# PGTN023_mix8.net
KiCad netlist of a schematic drawn in EAGLE
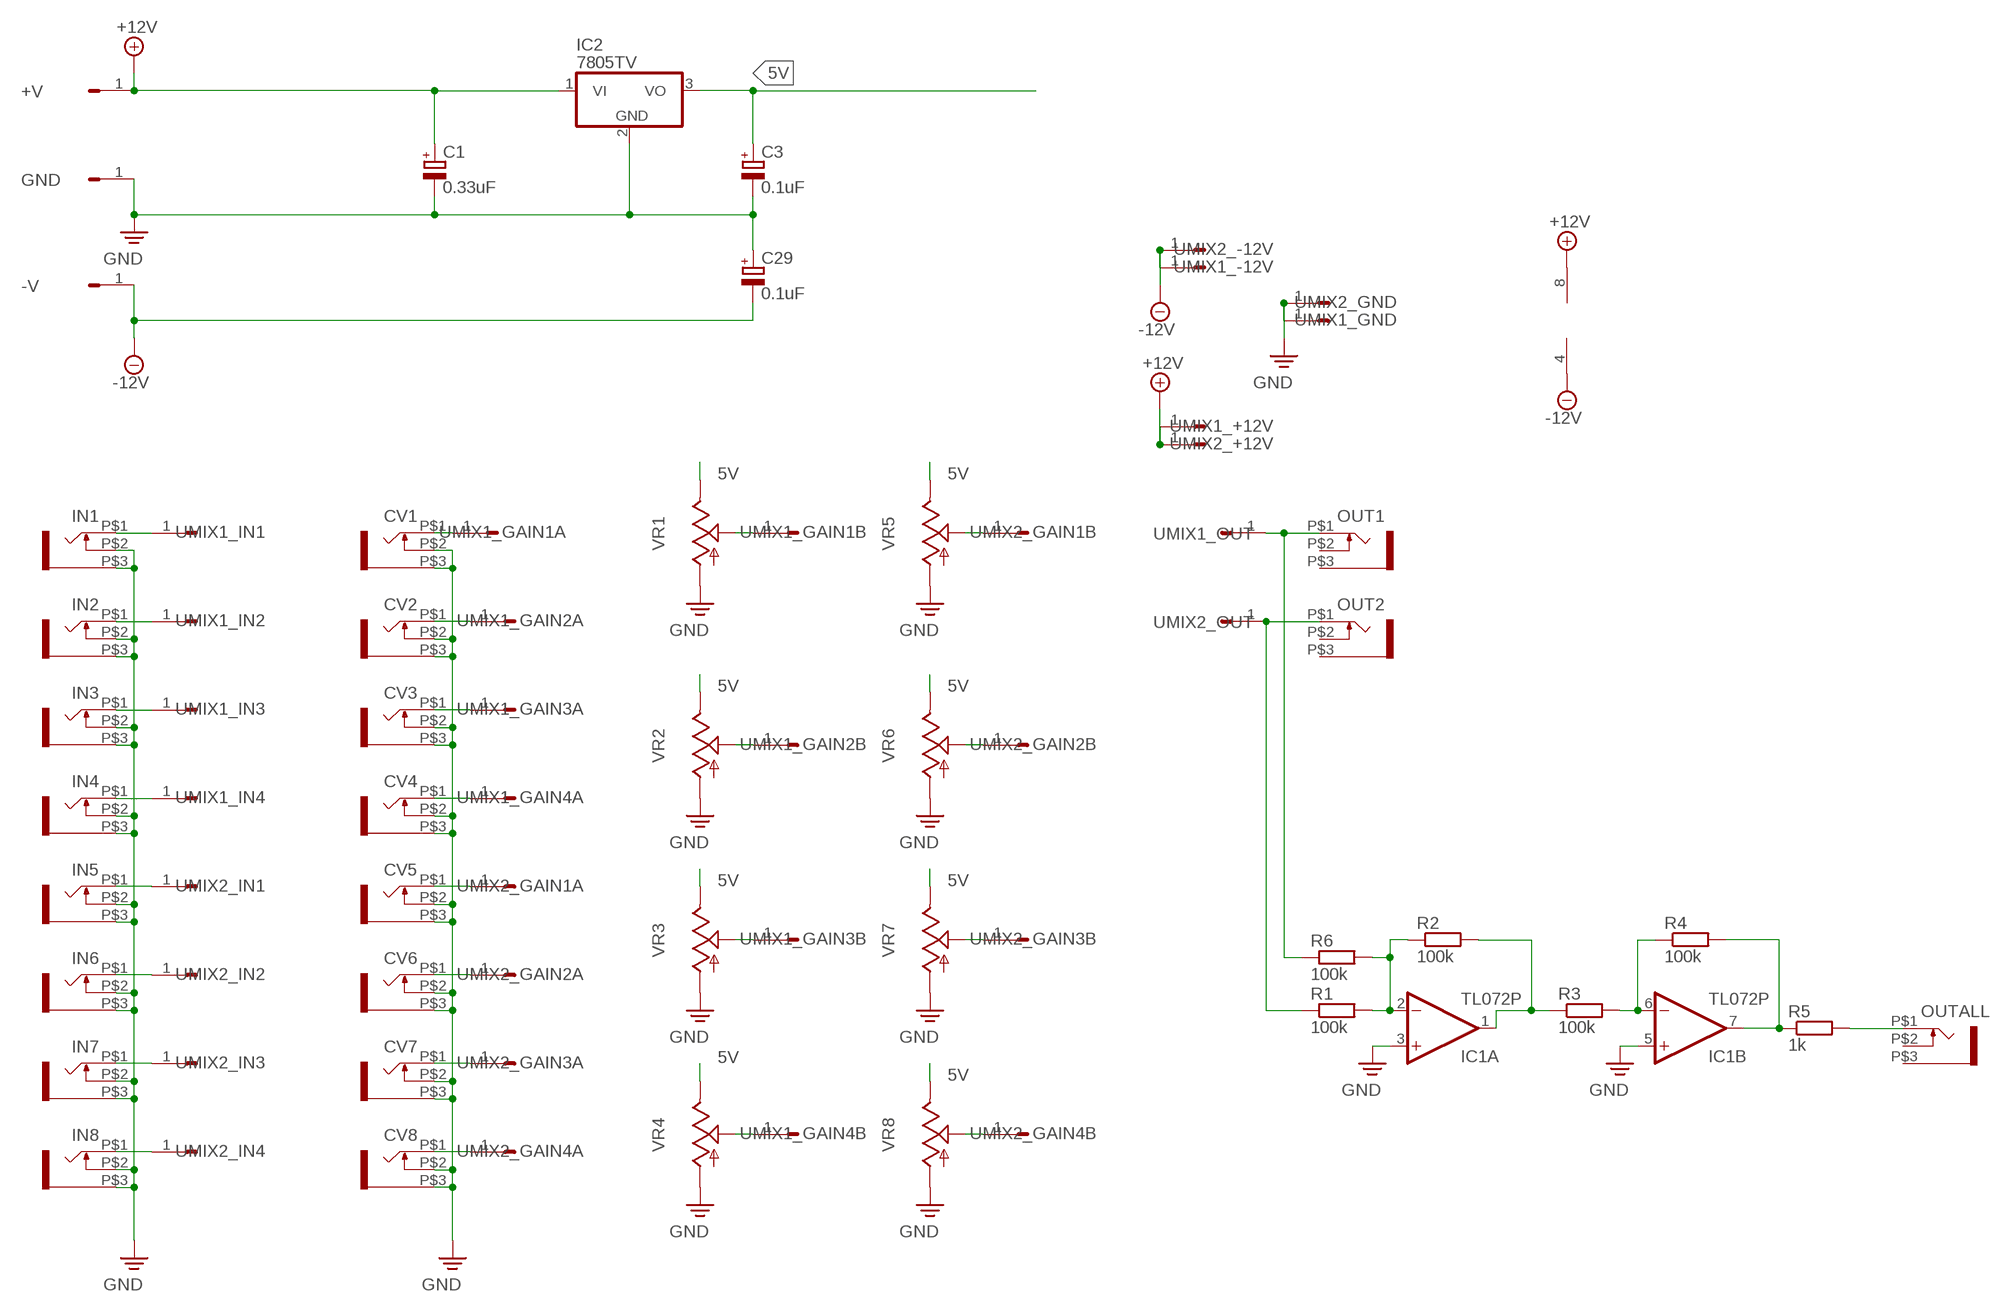
[diagram p0: schematic, sheet 1]

(export (version "E")
  (design (tool "Eeschema 10.0.6"))
  (components
    (comp (ref "+V")
      (value "HEADER/MALE/01")
      (footprint "eagle-import:HEADER_MALE_01")
      (fields (field (name "SPICEPREFIX") "X"))
      (libsource (lib "eagle-import") (part "HEADER/MALE/01"))
    )
    (comp (ref "-V")
      (value "HEADER/MALE/01")
      (footprint "eagle-import:HEADER_MALE_01")
      (fields (field (name "SPICEPREFIX") "X"))
      (libsource (lib "eagle-import") (part "HEADER/MALE/01"))
    )
    (comp (ref "C1")
      (value "0.33uF")
      (footprint "eagle-import:E2,5-6")
      (fields (field (name "SPICEPREFIX") "C"))
      (libsource (lib "eagle-import") (part "CAPACITOR/POLARIZEDE2.5-6"))
    )
    (comp (ref "C3")
      (value "0.1uF")
      (footprint "eagle-import:E2,5-6")
      (fields (field (name "SPICEPREFIX") "C"))
      (libsource (lib "eagle-import") (part "CAPACITOR/POLARIZEDE2.5-6"))
    )
    (comp (ref "C29")
      (value "0.1uF")
      (footprint "eagle-import:E2,5-6")
      (fields (field (name "SPICEPREFIX") "C"))
      (libsource (lib "eagle-import") (part "CAPACITOR/POLARIZEDE2.5-6"))
    )
    (comp (ref "CV1")
      (value "WQP-PJ301M-12_JACK")
      (footprint "eagle-import:WQP-PJ301M-12_JACK")
      (libsource (lib "eagle-import") (part "WQP-PJ301M-12_JACK"))
    )
    (comp (ref "CV2")
      (value "WQP-PJ301M-12_JACK")
      (footprint "eagle-import:WQP-PJ301M-12_JACK")
      (libsource (lib "eagle-import") (part "WQP-PJ301M-12_JACK"))
    )
    (comp (ref "CV3")
      (value "WQP-PJ301M-12_JACK")
      (footprint "eagle-import:WQP-PJ301M-12_JACK")
      (libsource (lib "eagle-import") (part "WQP-PJ301M-12_JACK"))
    )
    (comp (ref "CV4")
      (value "WQP-PJ301M-12_JACK")
      (footprint "eagle-import:WQP-PJ301M-12_JACK")
      (libsource (lib "eagle-import") (part "WQP-PJ301M-12_JACK"))
    )
    (comp (ref "CV5")
      (value "WQP-PJ301M-12_JACK")
      (footprint "eagle-import:WQP-PJ301M-12_JACK")
      (libsource (lib "eagle-import") (part "WQP-PJ301M-12_JACK"))
    )
    (comp (ref "CV6")
      (value "WQP-PJ301M-12_JACK")
      (footprint "eagle-import:WQP-PJ301M-12_JACK")
      (libsource (lib "eagle-import") (part "WQP-PJ301M-12_JACK"))
    )
    (comp (ref "CV7")
      (value "WQP-PJ301M-12_JACK")
      (footprint "eagle-import:WQP-PJ301M-12_JACK")
      (libsource (lib "eagle-import") (part "WQP-PJ301M-12_JACK"))
    )
    (comp (ref "CV8")
      (value "WQP-PJ301M-12_JACK")
      (footprint "eagle-import:WQP-PJ301M-12_JACK")
      (libsource (lib "eagle-import") (part "WQP-PJ301M-12_JACK"))
    )
    (comp (ref "GND")
      (value "HEADER/MALE/01")
      (footprint "eagle-import:HEADER_MALE_01")
      (fields (field (name "SPICEPREFIX") "X"))
      (libsource (lib "eagle-import") (part "HEADER/MALE/01"))
    )
    (comp (ref "IC1")
      (value "TL072P")
      (footprint "eagle-import:DIL08")
      (libsource (lib "eagle-import") (part "TL072P"))
    )
    (comp (ref "IC2")
      (value "7805TV")
      (footprint "eagle-import:TO220V")
      (libsource (lib "eagle-import") (part "78TV05"))
    )
    (comp (ref "IN1")
      (value "WQP-PJ301M-12_JACK")
      (footprint "eagle-import:WQP-PJ301M-12_JACK")
      (libsource (lib "eagle-import") (part "WQP-PJ301M-12_JACK"))
    )
    (comp (ref "IN2")
      (value "WQP-PJ301M-12_JACK")
      (footprint "eagle-import:WQP-PJ301M-12_JACK")
      (libsource (lib "eagle-import") (part "WQP-PJ301M-12_JACK"))
    )
    (comp (ref "IN3")
      (value "WQP-PJ301M-12_JACK")
      (footprint "eagle-import:WQP-PJ301M-12_JACK")
      (libsource (lib "eagle-import") (part "WQP-PJ301M-12_JACK"))
    )
    (comp (ref "IN4")
      (value "WQP-PJ301M-12_JACK")
      (footprint "eagle-import:WQP-PJ301M-12_JACK")
      (libsource (lib "eagle-import") (part "WQP-PJ301M-12_JACK"))
    )
    (comp (ref "IN5")
      (value "WQP-PJ301M-12_JACK")
      (footprint "eagle-import:WQP-PJ301M-12_JACK")
      (libsource (lib "eagle-import") (part "WQP-PJ301M-12_JACK"))
    )
    (comp (ref "IN6")
      (value "WQP-PJ301M-12_JACK")
      (footprint "eagle-import:WQP-PJ301M-12_JACK")
      (libsource (lib "eagle-import") (part "WQP-PJ301M-12_JACK"))
    )
    (comp (ref "IN7")
      (value "WQP-PJ301M-12_JACK")
      (footprint "eagle-import:WQP-PJ301M-12_JACK")
      (libsource (lib "eagle-import") (part "WQP-PJ301M-12_JACK"))
    )
    (comp (ref "IN8")
      (value "WQP-PJ301M-12_JACK")
      (footprint "eagle-import:WQP-PJ301M-12_JACK")
      (libsource (lib "eagle-import") (part "WQP-PJ301M-12_JACK"))
    )
    (comp (ref "OUT1")
      (value "WQP-PJ301M-12_JACK")
      (footprint "eagle-import:WQP-PJ301M-12_JACK")
      (libsource (lib "eagle-import") (part "WQP-PJ301M-12_JACK"))
    )
    (comp (ref "OUT2")
      (value "WQP-PJ301M-12_JACK")
      (footprint "eagle-import:WQP-PJ301M-12_JACK")
      (libsource (lib "eagle-import") (part "WQP-PJ301M-12_JACK"))
    )
    (comp (ref "OUTALL")
      (value "WQP-PJ301M-12_JACK")
      (footprint "eagle-import:WQP-PJ301M-12_JACK")
      (libsource (lib "eagle-import") (part "WQP-PJ301M-12_JACK"))
    )
    (comp (ref "R1")
      (value "100k")
      (footprint "eagle-import:RESISTOR_7.5")
      (libsource (lib "eagle-import") (part "RESISTORRESISTOR/UPRIGHT/7.5"))
    )
    (comp (ref "R2")
      (value "100k")
      (footprint "eagle-import:RESISTOR_7.5")
      (libsource (lib "eagle-import") (part "RESISTORRESISTOR/UPRIGHT/7.5"))
    )
    (comp (ref "R3")
      (value "100k")
      (footprint "eagle-import:RESISTOR_7.5")
      (libsource (lib "eagle-import") (part "RESISTORRESISTOR/UPRIGHT/7.5"))
    )
    (comp (ref "R4")
      (value "100k")
      (footprint "eagle-import:RESISTOR_7.5")
      (libsource (lib "eagle-import") (part "RESISTORRESISTOR/UPRIGHT/7.5"))
    )
    (comp (ref "R5")
      (value "1k")
      (footprint "eagle-import:RESISTOR_7.5")
      (libsource (lib "eagle-import") (part "RESISTORRESISTOR/UPRIGHT/7.5"))
    )
    (comp (ref "R6")
      (value "100k")
      (footprint "eagle-import:RESISTOR_7.5")
      (libsource (lib "eagle-import") (part "RESISTORRESISTOR/UPRIGHT/7.5"))
    )
    (comp (ref "UMIX1_+12V")
      (value "HEADER/MALE/01")
      (footprint "eagle-import:HEADER_MALE_01")
      (fields (field (name "SPICEPREFIX") "X"))
      (libsource (lib "eagle-import") (part "HEADER/MALE/01"))
    )
    (comp (ref "UMIX1_-12V")
      (value "HEADER/MALE/01")
      (footprint "eagle-import:HEADER_MALE_01")
      (fields (field (name "SPICEPREFIX") "X"))
      (libsource (lib "eagle-import") (part "HEADER/MALE/01"))
    )
    (comp (ref "UMIX1_GAIN1A")
      (value "HEADER/MALE/01")
      (footprint "eagle-import:HEADER_MALE_01")
      (fields (field (name "SPICEPREFIX") "X"))
      (libsource (lib "eagle-import") (part "HEADER/MALE/01"))
    )
    (comp (ref "UMIX1_GAIN1B")
      (value "HEADER/MALE/01")
      (footprint "eagle-import:HEADER_MALE_01")
      (fields (field (name "SPICEPREFIX") "X"))
      (libsource (lib "eagle-import") (part "HEADER/MALE/01"))
    )
    (comp (ref "UMIX1_GAIN2A")
      (value "HEADER/MALE/01")
      (footprint "eagle-import:HEADER_MALE_01")
      (fields (field (name "SPICEPREFIX") "X"))
      (libsource (lib "eagle-import") (part "HEADER/MALE/01"))
    )
    (comp (ref "UMIX1_GAIN2B")
      (value "HEADER/MALE/01")
      (footprint "eagle-import:HEADER_MALE_01")
      (fields (field (name "SPICEPREFIX") "X"))
      (libsource (lib "eagle-import") (part "HEADER/MALE/01"))
    )
    (comp (ref "UMIX1_GAIN3A")
      (value "HEADER/MALE/01")
      (footprint "eagle-import:HEADER_MALE_01")
      (fields (field (name "SPICEPREFIX") "X"))
      (libsource (lib "eagle-import") (part "HEADER/MALE/01"))
    )
    (comp (ref "UMIX1_GAIN3B")
      (value "HEADER/MALE/01")
      (footprint "eagle-import:HEADER_MALE_01")
      (fields (field (name "SPICEPREFIX") "X"))
      (libsource (lib "eagle-import") (part "HEADER/MALE/01"))
    )
    (comp (ref "UMIX1_GAIN4A")
      (value "HEADER/MALE/01")
      (footprint "eagle-import:HEADER_MALE_01")
      (fields (field (name "SPICEPREFIX") "X"))
      (libsource (lib "eagle-import") (part "HEADER/MALE/01"))
    )
    (comp (ref "UMIX1_GAIN4B")
      (value "HEADER/MALE/01")
      (footprint "eagle-import:HEADER_MALE_01")
      (fields (field (name "SPICEPREFIX") "X"))
      (libsource (lib "eagle-import") (part "HEADER/MALE/01"))
    )
    (comp (ref "UMIX1_GND")
      (value "HEADER/MALE/01")
      (footprint "eagle-import:HEADER_MALE_01")
      (fields (field (name "SPICEPREFIX") "X"))
      (libsource (lib "eagle-import") (part "HEADER/MALE/01"))
    )
    (comp (ref "UMIX1_IN1")
      (value "HEADER/MALE/01")
      (footprint "eagle-import:HEADER_MALE_01")
      (fields (field (name "SPICEPREFIX") "X"))
      (libsource (lib "eagle-import") (part "HEADER/MALE/01"))
    )
    (comp (ref "UMIX1_IN2")
      (value "HEADER/MALE/01")
      (footprint "eagle-import:HEADER_MALE_01")
      (fields (field (name "SPICEPREFIX") "X"))
      (libsource (lib "eagle-import") (part "HEADER/MALE/01"))
    )
    (comp (ref "UMIX1_IN3")
      (value "HEADER/MALE/01")
      (footprint "eagle-import:HEADER_MALE_01")
      (fields (field (name "SPICEPREFIX") "X"))
      (libsource (lib "eagle-import") (part "HEADER/MALE/01"))
    )
    (comp (ref "UMIX1_IN4")
      (value "HEADER/MALE/01")
      (footprint "eagle-import:HEADER_MALE_01")
      (fields (field (name "SPICEPREFIX") "X"))
      (libsource (lib "eagle-import") (part "HEADER/MALE/01"))
    )
    (comp (ref "UMIX1_OUT")
      (value "HEADER/MALE/01")
      (footprint "eagle-import:HEADER_MALE_01")
      (fields (field (name "SPICEPREFIX") "X"))
      (libsource (lib "eagle-import") (part "HEADER/MALE/01"))
    )
    (comp (ref "UMIX2_+12V")
      (value "HEADER/MALE/01")
      (footprint "eagle-import:HEADER_MALE_01")
      (fields (field (name "SPICEPREFIX") "X"))
      (libsource (lib "eagle-import") (part "HEADER/MALE/01"))
    )
    (comp (ref "UMIX2_-12V")
      (value "HEADER/MALE/01")
      (footprint "eagle-import:HEADER_MALE_01")
      (fields (field (name "SPICEPREFIX") "X"))
      (libsource (lib "eagle-import") (part "HEADER/MALE/01"))
    )
    (comp (ref "UMIX2_GAIN1A")
      (value "HEADER/MALE/01")
      (footprint "eagle-import:HEADER_MALE_01")
      (fields (field (name "SPICEPREFIX") "X"))
      (libsource (lib "eagle-import") (part "HEADER/MALE/01"))
    )
    (comp (ref "UMIX2_GAIN1B")
      (value "HEADER/MALE/01")
      (footprint "eagle-import:HEADER_MALE_01")
      (fields (field (name "SPICEPREFIX") "X"))
      (libsource (lib "eagle-import") (part "HEADER/MALE/01"))
    )
    (comp (ref "UMIX2_GAIN2A")
      (value "HEADER/MALE/01")
      (footprint "eagle-import:HEADER_MALE_01")
      (fields (field (name "SPICEPREFIX") "X"))
      (libsource (lib "eagle-import") (part "HEADER/MALE/01"))
    )
    (comp (ref "UMIX2_GAIN2B")
      (value "HEADER/MALE/01")
      (footprint "eagle-import:HEADER_MALE_01")
      (fields (field (name "SPICEPREFIX") "X"))
      (libsource (lib "eagle-import") (part "HEADER/MALE/01"))
    )
    (comp (ref "UMIX2_GAIN3A")
      (value "HEADER/MALE/01")
      (footprint "eagle-import:HEADER_MALE_01")
      (fields (field (name "SPICEPREFIX") "X"))
      (libsource (lib "eagle-import") (part "HEADER/MALE/01"))
    )
    (comp (ref "UMIX2_GAIN3B")
      (value "HEADER/MALE/01")
      (footprint "eagle-import:HEADER_MALE_01")
      (fields (field (name "SPICEPREFIX") "X"))
      (libsource (lib "eagle-import") (part "HEADER/MALE/01"))
    )
    (comp (ref "UMIX2_GAIN4A")
      (value "HEADER/MALE/01")
      (footprint "eagle-import:HEADER_MALE_01")
      (fields (field (name "SPICEPREFIX") "X"))
      (libsource (lib "eagle-import") (part "HEADER/MALE/01"))
    )
    (comp (ref "UMIX2_GAIN4B")
      (value "HEADER/MALE/01")
      (footprint "eagle-import:HEADER_MALE_01")
      (fields (field (name "SPICEPREFIX") "X"))
      (libsource (lib "eagle-import") (part "HEADER/MALE/01"))
    )
    (comp (ref "UMIX2_GND")
      (value "HEADER/MALE/01")
      (footprint "eagle-import:HEADER_MALE_01")
      (fields (field (name "SPICEPREFIX") "X"))
      (libsource (lib "eagle-import") (part "HEADER/MALE/01"))
    )
    (comp (ref "UMIX2_IN1")
      (value "HEADER/MALE/01")
      (footprint "eagle-import:HEADER_MALE_01")
      (fields (field (name "SPICEPREFIX") "X"))
      (libsource (lib "eagle-import") (part "HEADER/MALE/01"))
    )
    (comp (ref "UMIX2_IN2")
      (value "HEADER/MALE/01")
      (footprint "eagle-import:HEADER_MALE_01")
      (fields (field (name "SPICEPREFIX") "X"))
      (libsource (lib "eagle-import") (part "HEADER/MALE/01"))
    )
    (comp (ref "UMIX2_IN3")
      (value "HEADER/MALE/01")
      (footprint "eagle-import:HEADER_MALE_01")
      (fields (field (name "SPICEPREFIX") "X"))
      (libsource (lib "eagle-import") (part "HEADER/MALE/01"))
    )
    (comp (ref "UMIX2_IN4")
      (value "HEADER/MALE/01")
      (footprint "eagle-import:HEADER_MALE_01")
      (fields (field (name "SPICEPREFIX") "X"))
      (libsource (lib "eagle-import") (part "HEADER/MALE/01"))
    )
    (comp (ref "UMIX2_OUT")
      (value "HEADER/MALE/01")
      (footprint "eagle-import:HEADER_MALE_01")
      (fields (field (name "SPICEPREFIX") "X"))
      (libsource (lib "eagle-import") (part "HEADER/MALE/01"))
    )
    (comp (ref "VR1")
      (value "9MM_SNAP-IN_POT_")
      (footprint "eagle-import:9MM_SNAP-IN_POT")
      (libsource (lib "eagle-import") (part "9MM_SNAP-IN_POT_"))
    )
    (comp (ref "VR2")
      (value "9MM_SNAP-IN_POT_")
      (footprint "eagle-import:9MM_SNAP-IN_POT")
      (libsource (lib "eagle-import") (part "9MM_SNAP-IN_POT_"))
    )
    (comp (ref "VR3")
      (value "9MM_SNAP-IN_POT_")
      (footprint "eagle-import:9MM_SNAP-IN_POT")
      (libsource (lib "eagle-import") (part "9MM_SNAP-IN_POT_"))
    )
    (comp (ref "VR4")
      (value "9MM_SNAP-IN_POT_")
      (footprint "eagle-import:9MM_SNAP-IN_POT")
      (libsource (lib "eagle-import") (part "9MM_SNAP-IN_POT_"))
    )
    (comp (ref "VR5")
      (value "9MM_SNAP-IN_POT_")
      (footprint "eagle-import:9MM_SNAP-IN_POT")
      (libsource (lib "eagle-import") (part "9MM_SNAP-IN_POT_"))
    )
    (comp (ref "VR6")
      (value "9MM_SNAP-IN_POT_")
      (footprint "eagle-import:9MM_SNAP-IN_POT")
      (libsource (lib "eagle-import") (part "9MM_SNAP-IN_POT_"))
    )
    (comp (ref "VR7")
      (value "9MM_SNAP-IN_POT_")
      (footprint "eagle-import:9MM_SNAP-IN_POT")
      (libsource (lib "eagle-import") (part "9MM_SNAP-IN_POT_"))
    )
    (comp (ref "VR8")
      (value "9MM_SNAP-IN_POT_")
      (footprint "eagle-import:9MM_SNAP-IN_POT")
      (libsource (lib "eagle-import") (part "9MM_SNAP-IN_POT_"))
    )
  )
  (nets
    (net (code "1") (name "+12V") (class "Default")
      (node (ref "+V") (pin "1") (pinfunction "3_1") (pintype "passive"))
      (node (ref "C1") (pin "+") (pinfunction "+_+") (pintype "passive"))
      (node (ref "IC1") (pin "8") (pinfunction "V+_8") (pintype "power_in"))
      (node (ref "IC2") (pin "1") (pinfunction "VI_1") (pintype "input"))
      (node (ref "UMIX1_+12V") (pin "1") (pinfunction "3_1") (pintype "passive"))
      (node (ref "UMIX2_+12V") (pin "1") (pinfunction "3_1") (pintype "passive"))
    )
    (net (code "2") (name "-12V") (class "Default")
      (node (ref "-V") (pin "1") (pinfunction "3_1") (pintype "passive"))
      (node (ref "C29") (pin "-") (pinfunction "-_-") (pintype "passive"))
      (node (ref "IC1") (pin "4") (pinfunction "V-_4") (pintype "power_in"))
      (node (ref "UMIX1_-12V") (pin "1") (pinfunction "3_1") (pintype "passive"))
      (node (ref "UMIX2_-12V") (pin "1") (pinfunction "3_1") (pintype "passive"))
    )
    (net (code "3") (name "5V") (class "Default")
      (node (ref "C3") (pin "+") (pinfunction "+_+") (pintype "passive"))
      (node (ref "IC2") (pin "3") (pinfunction "VO_3") (pintype "passive"))
      (node (ref "VR1") (pin "3") (pinfunction "E_3") (pintype "passive"))
      (node (ref "VR2") (pin "3") (pinfunction "E_3") (pintype "passive"))
      (node (ref "VR3") (pin "3") (pinfunction "E_3") (pintype "passive"))
      (node (ref "VR4") (pin "3") (pinfunction "E_3") (pintype "passive"))
      (node (ref "VR5") (pin "3") (pinfunction "E_3") (pintype "passive"))
      (node (ref "VR6") (pin "3") (pinfunction "E_3") (pintype "passive"))
      (node (ref "VR7") (pin "3") (pinfunction "E_3") (pintype "passive"))
      (node (ref "VR8") (pin "3") (pinfunction "E_3") (pintype "passive"))
    )
    (net (code "4") (name "GND") (class "Default")
      (node (ref "C1") (pin "-") (pinfunction "-_-") (pintype "passive"))
      (node (ref "C29") (pin "+") (pinfunction "+_+") (pintype "passive"))
      (node (ref "C3") (pin "-") (pinfunction "-_-") (pintype "passive"))
      (node (ref "CV1") (pin "P$2") (pinfunction "3_P$2") (pintype "passive"))
      (node (ref "CV1") (pin "P$3") (pinfunction "1_P$3") (pintype "passive"))
      (node (ref "CV2") (pin "P$2") (pinfunction "3_P$2") (pintype "passive"))
      (node (ref "CV2") (pin "P$3") (pinfunction "1_P$3") (pintype "passive"))
      (node (ref "CV3") (pin "P$2") (pinfunction "3_P$2") (pintype "passive"))
      (node (ref "CV3") (pin "P$3") (pinfunction "1_P$3") (pintype "passive"))
      (node (ref "CV4") (pin "P$2") (pinfunction "3_P$2") (pintype "passive"))
      (node (ref "CV4") (pin "P$3") (pinfunction "1_P$3") (pintype "passive"))
      (node (ref "CV5") (pin "P$2") (pinfunction "3_P$2") (pintype "passive"))
      (node (ref "CV5") (pin "P$3") (pinfunction "1_P$3") (pintype "passive"))
      (node (ref "CV6") (pin "P$2") (pinfunction "3_P$2") (pintype "passive"))
      (node (ref "CV6") (pin "P$3") (pinfunction "1_P$3") (pintype "passive"))
      (node (ref "CV7") (pin "P$2") (pinfunction "3_P$2") (pintype "passive"))
      (node (ref "CV7") (pin "P$3") (pinfunction "1_P$3") (pintype "passive"))
      (node (ref "CV8") (pin "P$2") (pinfunction "3_P$2") (pintype "passive"))
      (node (ref "CV8") (pin "P$3") (pinfunction "1_P$3") (pintype "passive"))
      (node (ref "GND") (pin "1") (pinfunction "3_1") (pintype "passive"))
      (node (ref "IC1") (pin "3") (pinfunction "+IN_3") (pintype "input"))
      (node (ref "IC1") (pin "5") (pinfunction "+IN_5") (pintype "input"))
      (node (ref "IC2") (pin "2") (pinfunction "GND_2") (pintype "passive"))
      (node (ref "IN1") (pin "P$2") (pinfunction "3_P$2") (pintype "passive"))
      (node (ref "IN1") (pin "P$3") (pinfunction "1_P$3") (pintype "passive"))
      (node (ref "IN2") (pin "P$2") (pinfunction "3_P$2") (pintype "passive"))
      (node (ref "IN2") (pin "P$3") (pinfunction "1_P$3") (pintype "passive"))
      (node (ref "IN3") (pin "P$2") (pinfunction "3_P$2") (pintype "passive"))
      (node (ref "IN3") (pin "P$3") (pinfunction "1_P$3") (pintype "passive"))
      (node (ref "IN4") (pin "P$2") (pinfunction "3_P$2") (pintype "passive"))
      (node (ref "IN4") (pin "P$3") (pinfunction "1_P$3") (pintype "passive"))
      (node (ref "IN5") (pin "P$2") (pinfunction "3_P$2") (pintype "passive"))
      (node (ref "IN5") (pin "P$3") (pinfunction "1_P$3") (pintype "passive"))
      (node (ref "IN6") (pin "P$2") (pinfunction "3_P$2") (pintype "passive"))
      (node (ref "IN6") (pin "P$3") (pinfunction "1_P$3") (pintype "passive"))
      (node (ref "IN7") (pin "P$2") (pinfunction "3_P$2") (pintype "passive"))
      (node (ref "IN7") (pin "P$3") (pinfunction "1_P$3") (pintype "passive"))
      (node (ref "IN8") (pin "P$2") (pinfunction "3_P$2") (pintype "passive"))
      (node (ref "IN8") (pin "P$3") (pinfunction "1_P$3") (pintype "passive"))
      (node (ref "UMIX1_GND") (pin "1") (pinfunction "3_1") (pintype "passive"))
      (node (ref "UMIX2_GND") (pin "1") (pinfunction "3_1") (pintype "passive"))
      (node (ref "VR1") (pin "1") (pinfunction "A_1") (pintype "passive"))
      (node (ref "VR2") (pin "1") (pinfunction "A_1") (pintype "passive"))
      (node (ref "VR3") (pin "1") (pinfunction "A_1") (pintype "passive"))
      (node (ref "VR4") (pin "1") (pinfunction "A_1") (pintype "passive"))
      (node (ref "VR5") (pin "1") (pinfunction "A_1") (pintype "passive"))
      (node (ref "VR6") (pin "1") (pinfunction "A_1") (pintype "passive"))
      (node (ref "VR7") (pin "1") (pinfunction "A_1") (pintype "passive"))
      (node (ref "VR8") (pin "1") (pinfunction "A_1") (pintype "passive"))
    )
    (net (code "5") (name "Net-(CV1-2)") (class "Default")
      (node (ref "CV1") (pin "P$1") (pinfunction "2_P$1") (pintype "passive"))
      (node (ref "UMIX1_GAIN1A") (pin "1") (pinfunction "3_1") (pintype "passive"))
    )
    (net (code "6") (name "Net-(CV2-2)") (class "Default")
      (node (ref "CV2") (pin "P$1") (pinfunction "2_P$1") (pintype "passive"))
      (node (ref "UMIX1_GAIN2A") (pin "1") (pinfunction "3_1") (pintype "passive"))
    )
    (net (code "7") (name "Net-(CV3-2)") (class "Default")
      (node (ref "CV3") (pin "P$1") (pinfunction "2_P$1") (pintype "passive"))
      (node (ref "UMIX1_GAIN3A") (pin "1") (pinfunction "3_1") (pintype "passive"))
    )
    (net (code "8") (name "Net-(CV4-2)") (class "Default")
      (node (ref "CV4") (pin "P$1") (pinfunction "2_P$1") (pintype "passive"))
      (node (ref "UMIX1_GAIN4A") (pin "1") (pinfunction "3_1") (pintype "passive"))
    )
    (net (code "9") (name "Net-(CV5-2)") (class "Default")
      (node (ref "CV5") (pin "P$1") (pinfunction "2_P$1") (pintype "passive"))
      (node (ref "UMIX2_GAIN1A") (pin "1") (pinfunction "3_1") (pintype "passive"))
    )
    (net (code "10") (name "Net-(CV6-2)") (class "Default")
      (node (ref "CV6") (pin "P$1") (pinfunction "2_P$1") (pintype "passive"))
      (node (ref "UMIX2_GAIN2A") (pin "1") (pinfunction "3_1") (pintype "passive"))
    )
    (net (code "11") (name "Net-(CV7-2)") (class "Default")
      (node (ref "CV7") (pin "P$1") (pinfunction "2_P$1") (pintype "passive"))
      (node (ref "UMIX2_GAIN3A") (pin "1") (pinfunction "3_1") (pintype "passive"))
    )
    (net (code "12") (name "Net-(CV8-2)") (class "Default")
      (node (ref "CV8") (pin "P$1") (pinfunction "2_P$1") (pintype "passive"))
      (node (ref "UMIX2_GAIN4A") (pin "1") (pinfunction "3_1") (pintype "passive"))
    )
    (net (code "13") (name "Net-(IC1A--IN)") (class "Default")
      (node (ref "IC1") (pin "2") (pinfunction "-IN_2") (pintype "input"))
      (node (ref "R1") (pin "2") (pinfunction "2_2") (pintype "passive"))
      (node (ref "R2") (pin "1") (pinfunction "1_1") (pintype "passive"))
      (node (ref "R6") (pin "2") (pinfunction "2_2") (pintype "passive"))
    )
    (net (code "14") (name "Net-(IC1A-OUT)") (class "Default")
      (node (ref "IC1") (pin "1") (pinfunction "OUT_1") (pintype "output"))
      (node (ref "R2") (pin "2") (pinfunction "2_2") (pintype "passive"))
      (node (ref "R3") (pin "1") (pinfunction "1_1") (pintype "passive"))
    )
    (net (code "15") (name "Net-(IC1B--IN)") (class "Default")
      (node (ref "IC1") (pin "6") (pinfunction "-IN_6") (pintype "input"))
      (node (ref "R3") (pin "2") (pinfunction "2_2") (pintype "passive"))
      (node (ref "R4") (pin "1") (pinfunction "1_1") (pintype "passive"))
    )
    (net (code "16") (name "Net-(IC1B-OUT)") (class "Default")
      (node (ref "IC1") (pin "7") (pinfunction "OUT_7") (pintype "output"))
      (node (ref "R4") (pin "2") (pinfunction "2_2") (pintype "passive"))
      (node (ref "R5") (pin "1") (pinfunction "1_1") (pintype "passive"))
    )
    (net (code "17") (name "Net-(IN1-2)") (class "Default")
      (node (ref "IN1") (pin "P$1") (pinfunction "2_P$1") (pintype "passive"))
      (node (ref "UMIX1_IN1") (pin "1") (pinfunction "3_1") (pintype "passive"))
    )
    (net (code "18") (name "Net-(IN2-2)") (class "Default")
      (node (ref "IN2") (pin "P$1") (pinfunction "2_P$1") (pintype "passive"))
      (node (ref "UMIX1_IN2") (pin "1") (pinfunction "3_1") (pintype "passive"))
    )
    (net (code "19") (name "Net-(IN3-2)") (class "Default")
      (node (ref "IN3") (pin "P$1") (pinfunction "2_P$1") (pintype "passive"))
      (node (ref "UMIX1_IN3") (pin "1") (pinfunction "3_1") (pintype "passive"))
    )
    (net (code "20") (name "Net-(IN4-2)") (class "Default")
      (node (ref "IN4") (pin "P$1") (pinfunction "2_P$1") (pintype "passive"))
      (node (ref "UMIX1_IN4") (pin "1") (pinfunction "3_1") (pintype "passive"))
    )
    (net (code "21") (name "Net-(IN5-2)") (class "Default")
      (node (ref "IN5") (pin "P$1") (pinfunction "2_P$1") (pintype "passive"))
      (node (ref "UMIX2_IN1") (pin "1") (pinfunction "3_1") (pintype "passive"))
    )
    (net (code "22") (name "Net-(IN6-2)") (class "Default")
      (node (ref "IN6") (pin "P$1") (pinfunction "2_P$1") (pintype "passive"))
      (node (ref "UMIX2_IN2") (pin "1") (pinfunction "3_1") (pintype "passive"))
    )
    (net (code "23") (name "Net-(IN7-2)") (class "Default")
      (node (ref "IN7") (pin "P$1") (pinfunction "2_P$1") (pintype "passive"))
      (node (ref "UMIX2_IN3") (pin "1") (pinfunction "3_1") (pintype "passive"))
    )
    (net (code "24") (name "Net-(IN8-2)") (class "Default")
      (node (ref "IN8") (pin "P$1") (pinfunction "2_P$1") (pintype "passive"))
      (node (ref "UMIX2_IN4") (pin "1") (pinfunction "3_1") (pintype "passive"))
    )
    (net (code "25") (name "Net-(OUT1-2)") (class "Default")
      (node (ref "OUT1") (pin "P$1") (pinfunction "2_P$1") (pintype "passive"))
      (node (ref "R6") (pin "1") (pinfunction "1_1") (pintype "passive"))
      (node (ref "UMIX1_OUT") (pin "1") (pinfunction "3_1") (pintype "passive"))
    )
    (net (code "26") (name "Net-(OUT2-2)") (class "Default")
      (node (ref "OUT2") (pin "P$1") (pinfunction "2_P$1") (pintype "passive"))
      (node (ref "R1") (pin "1") (pinfunction "1_1") (pintype "passive"))
      (node (ref "UMIX2_OUT") (pin "1") (pinfunction "3_1") (pintype "passive"))
    )
    (net (code "27") (name "Net-(OUTALL-2)") (class "Default")
      (node (ref "OUTALL") (pin "P$1") (pinfunction "2_P$1") (pintype "passive"))
      (node (ref "R5") (pin "2") (pinfunction "2_2") (pintype "passive"))
    )
    (net (code "28") (name "Net-(UMIX1_GAIN1B-3)") (class "Default")
      (node (ref "UMIX1_GAIN1B") (pin "1") (pinfunction "3_1") (pintype "passive"))
      (node (ref "VR1") (pin "2") (pinfunction "S_2") (pintype "passive"))
    )
    (net (code "29") (name "Net-(UMIX1_GAIN2B-3)") (class "Default")
      (node (ref "UMIX1_GAIN2B") (pin "1") (pinfunction "3_1") (pintype "passive"))
      (node (ref "VR2") (pin "2") (pinfunction "S_2") (pintype "passive"))
    )
    (net (code "30") (name "Net-(UMIX1_GAIN3B-3)") (class "Default")
      (node (ref "UMIX1_GAIN3B") (pin "1") (pinfunction "3_1") (pintype "passive"))
      (node (ref "VR3") (pin "2") (pinfunction "S_2") (pintype "passive"))
    )
    (net (code "31") (name "Net-(UMIX1_GAIN4B-3)") (class "Default")
      (node (ref "UMIX1_GAIN4B") (pin "1") (pinfunction "3_1") (pintype "passive"))
      (node (ref "VR4") (pin "2") (pinfunction "S_2") (pintype "passive"))
    )
    (net (code "32") (name "Net-(UMIX2_GAIN1B-3)") (class "Default")
      (node (ref "UMIX2_GAIN1B") (pin "1") (pinfunction "3_1") (pintype "passive"))
      (node (ref "VR5") (pin "2") (pinfunction "S_2") (pintype "passive"))
    )
    (net (code "33") (name "Net-(UMIX2_GAIN2B-3)") (class "Default")
      (node (ref "UMIX2_GAIN2B") (pin "1") (pinfunction "3_1") (pintype "passive"))
      (node (ref "VR6") (pin "2") (pinfunction "S_2") (pintype "passive"))
    )
    (net (code "34") (name "Net-(UMIX2_GAIN3B-3)") (class "Default")
      (node (ref "UMIX2_GAIN3B") (pin "1") (pinfunction "3_1") (pintype "passive"))
      (node (ref "VR7") (pin "2") (pinfunction "S_2") (pintype "passive"))
    )
    (net (code "35") (name "Net-(UMIX2_GAIN4B-3)") (class "Default")
      (node (ref "UMIX2_GAIN4B") (pin "1") (pinfunction "3_1") (pintype "passive"))
      (node (ref "VR8") (pin "2") (pinfunction "S_2") (pintype "passive"))
    )
    (net (code "36") (name "unconnected-(OUT1-1-PadP$3)") (class "Default")
      (node (ref "OUT1") (pin "P$3") (pinfunction "1_P$3") (pintype "passive"))
    )
    (net (code "37") (name "unconnected-(OUT1-3-PadP$2)") (class "Default")
      (node (ref "OUT1") (pin "P$2") (pinfunction "3_P$2") (pintype "passive"))
    )
    (net (code "38") (name "unconnected-(OUT2-1-PadP$3)") (class "Default")
      (node (ref "OUT2") (pin "P$3") (pinfunction "1_P$3") (pintype "passive"))
    )
    (net (code "39") (name "unconnected-(OUT2-3-PadP$2)") (class "Default")
      (node (ref "OUT2") (pin "P$2") (pinfunction "3_P$2") (pintype "passive"))
    )
    (net (code "40") (name "unconnected-(OUTALL-1-PadP$3)") (class "Default")
      (node (ref "OUTALL") (pin "P$3") (pinfunction "1_P$3") (pintype "passive"))
    )
    (net (code "41") (name "unconnected-(OUTALL-3-PadP$2)") (class "Default")
      (node (ref "OUTALL") (pin "P$2") (pinfunction "3_P$2") (pintype "passive"))
    )
  )
)
